# 06_Buzzer.net
KiCad netlist of a schematic drawn in Altium Designer
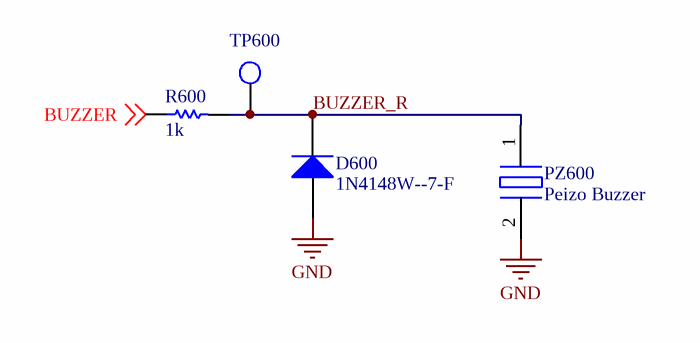
[diagram p0: 06_Buzzer.SchDoc]

(export (version "E")
  (design (tool "Eeschema 10.0.6"))
  (components
    (comp (ref "D600")
      (value "DIODE_4148")
      (footprint "SOD323-12")
      (description "DIODE GEN PURP 100V 300MA SOD123")
      (fields (field (name "MANUFACTURER") "Diodes") (field (name "MANUFACTURER PART NUMBER") "1N4148W--7-F"))
      (libsource (lib "ece315-2017-fall") (part "DIODE_4148"))
    )
    (comp (ref "PZ600")
      (value "Peizo Buzzer")
      (footprint "PKLCS")
      (description "AUDIO PIEZO TRANSDUCER 12.5V SMD")
      (fields
        (field (name "MANUFACTURER PART NUMBER") "PKLCS1212E2000-R1")
        (field (name "MANUFACTURER") "Murata Electronics North America")
      )
      (libsource (lib "ece315-2017-fall") (part "Peizo"))
    )
    (comp (ref "R600")
      (value "RES_0805_K_001.00")
      (footprint "RES_0805")
      (description "RES SMD 1K OHM 1% 1/8W 0805")
      (fields
        (field (name "MANUFACTURER PART NUMBER") "ERJ-6ENF1001V")
        (field (name "TOLERANCE") "±1%")
        (field (name "RESISTANCE (OHMS)") "1k")
      )
      (libsource (lib "ece315-2017-fall") (part "RES_0805_K_001.00"))
    )
    (comp (ref "TP600")
      (value "TP_1206")
      (footprint "TP-SMC-1206")
      (description "Test Point SMD 1206")
      (fields
        (field (name "MANUFACTURER") "TE Connectivity (Tyco Electronics)")
        (field (name "MANUFACTURER PART NUMBER") "1625854-1")
      )
      (libsource (lib "ece315-2017-fall") (part "TP_1206"))
    )
  )
  (nets
    (net (code "1") (name "/BUZZER_R") (class "Default")
      (node (ref "D600") (pin "1") (pinfunction "K_1") (pintype "passive"))
      (node (ref "PZ600") (pin "1") (pinfunction "In_1") (pintype "passive"))
      (node (ref "R600") (pin "2") (pinfunction "2_2") (pintype "passive"))
      (node (ref "TP600") (pin "1") (pintype "passive"))
    )
    (net (code "2") (name "BUZZER") (class "Default")
      (node (ref "R600") (pin "1") (pinfunction "1_1") (pintype "passive"))
    )
    (net (code "3") (name "GND") (class "Default")
      (node (ref "D600") (pin "2") (pinfunction "A_2") (pintype "passive"))
      (node (ref "PZ600") (pin "2") (pinfunction "In_2") (pintype "passive"))
    )
  )
)
